# connectors.net
KiCad netlist of a schematic drawn in Altium Designer
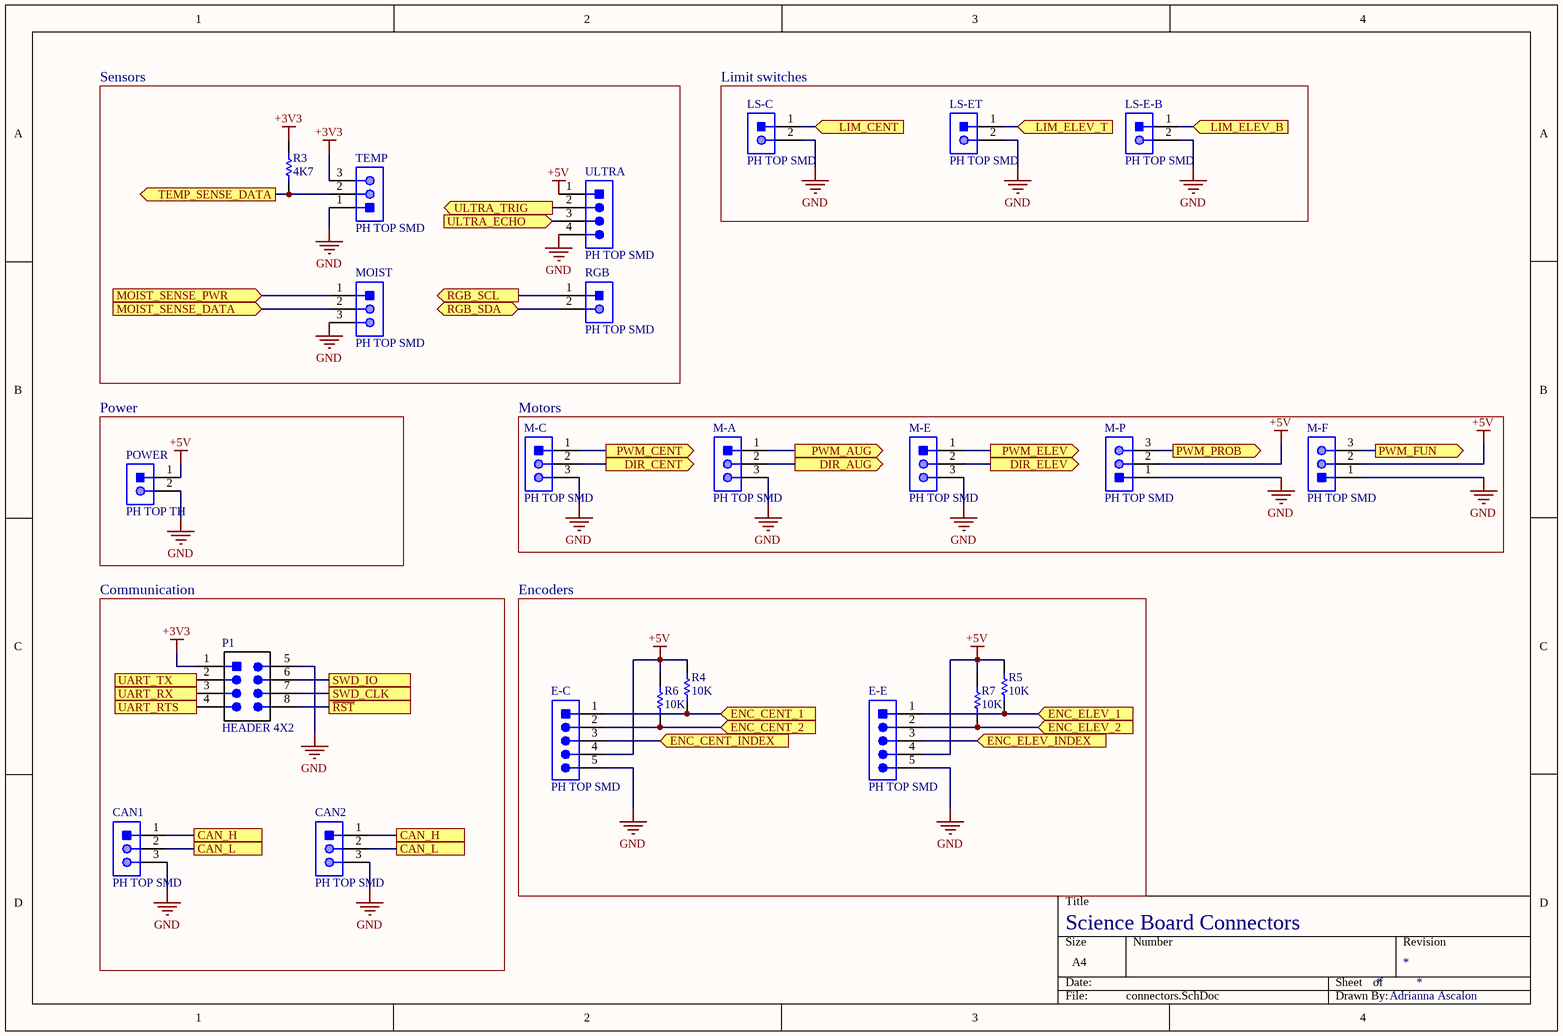
[diagram p0: connectors.SchDoc]

(export (version "E")
  (design (tool "Eeschema 10.0.6"))
  (components
    (comp (ref "CAN1")
      (value "PH TOP SMD")
      (footprint "JST-B3B-SM4-TB")
      (description "CONN HEADER PH TOP 3POS 2MM SMD")
      (fields (field (name "MANUFACTURER") "JST") (field (name "PART NUMBER") "B3B-PH-SM4-TB"))
      (libsource (lib "UWRT_Schematic_Library_2019") (part "CON_3M_PH_TOP_SMT"))
    )
    (comp (ref "CAN2")
      (value "PH TOP SMD")
      (footprint "JST-B3B-SM4-TB")
      (description "CONN HEADER PH TOP 3POS 2MM SMD")
      (fields (field (name "MANUFACTURER") "JST") (field (name "PART NUMBER") "B3B-PH-SM4-TB"))
      (libsource (lib "UWRT_Schematic_Library_2019") (part "CON_3M_PH_TOP_SMT"))
    )
    (comp (ref "E-C")
      (value "PH TOP SMD")
      (footprint "JST-B5B-SM4-TB")
      (description "CONN HEADER PH TOP 5POS 2MM SMD")
      (fields (field (name "MANUFACTURER") "JST") (field (name "PART NUMBER") "B5B-PH-SM4-TB"))
      (libsource (lib "UWRT_Schematic_Library_2019") (part "CON_5M_PH_TOP_SMT"))
    )
    (comp (ref "E-E")
      (value "PH TOP SMD")
      (footprint "JST-B5B-SM4-TB")
      (description "CONN HEADER PH TOP 5POS 2MM SMD")
      (fields (field (name "MANUFACTURER") "JST") (field (name "PART NUMBER") "B5B-PH-SM4-TB"))
      (libsource (lib "UWRT_Schematic_Library_2019") (part "CON_5M_PH_TOP_SMT"))
    )
    (comp (ref "LS-C")
      (value "PH TOP SMD")
      (footprint "JST-B2B-SM4-TB")
      (description "CONN HEADER PH TOP 2POS 2MM SMD")
      (fields (field (name "MANUFACTURER") "JST") (field (name "PART NUMBER") "B2B-PH-SM4-TB"))
      (libsource (lib "UWRT_Schematic_Library_2019") (part "CON_2M_PH_TOP_SMT"))
    )
    (comp (ref "LS-E-B")
      (value "PH TOP SMD")
      (footprint "JST-B2B-SM4-TB")
      (description "CONN HEADER PH TOP 2POS 2MM SMD")
      (fields (field (name "MANUFACTURER") "JST") (field (name "PART NUMBER") "B2B-PH-SM4-TB"))
      (libsource (lib "UWRT_Schematic_Library_2019") (part "CON_2M_PH_TOP_SMT"))
    )
    (comp (ref "LS-ET")
      (value "PH TOP SMD")
      (footprint "JST-B2B-SM4-TB")
      (description "CONN HEADER PH TOP 2POS 2MM SMD")
      (fields (field (name "MANUFACTURER") "JST") (field (name "PART NUMBER") "B2B-PH-SM4-TB"))
      (libsource (lib "UWRT_Schematic_Library_2019") (part "CON_2M_PH_TOP_SMT"))
    )
    (comp (ref "M-A")
      (value "PH TOP SMD")
      (footprint "JST-B3B-SM4-TB")
      (description "CONN HEADER PH TOP 3POS 2MM SMD")
      (fields (field (name "MANUFACTURER") "JST") (field (name "PART NUMBER") "B3B-PH-SM4-TB"))
      (libsource (lib "UWRT_Schematic_Library_2019") (part "CON_3M_PH_TOP_SMT"))
    )
    (comp (ref "M-C")
      (value "PH TOP SMD")
      (footprint "JST-B3B-SM4-TB")
      (description "CONN HEADER PH TOP 3POS 2MM SMD")
      (fields (field (name "MANUFACTURER") "JST") (field (name "PART NUMBER") "B3B-PH-SM4-TB"))
      (libsource (lib "UWRT_Schematic_Library_2019") (part "CON_3M_PH_TOP_SMT"))
    )
    (comp (ref "M-E")
      (value "PH TOP SMD")
      (footprint "JST-B3B-SM4-TB")
      (description "CONN HEADER PH TOP 3POS 2MM SMD")
      (fields (field (name "MANUFACTURER") "JST") (field (name "PART NUMBER") "B3B-PH-SM4-TB"))
      (libsource (lib "UWRT_Schematic_Library_2019") (part "CON_3M_PH_TOP_SMT"))
    )
    (comp (ref "M-F")
      (value "PH TOP SMD")
      (footprint "JST-B3B-SM4-TB")
      (description "CONN HEADER PH TOP 3POS 2MM SMD")
      (fields (field (name "MANUFACTURER") "JST") (field (name "PART NUMBER") "B3B-PH-SM4-TB"))
      (libsource (lib "") (part "CON_3M_PH_TOP_SMT_1"))
    )
    (comp (ref "M-P")
      (value "PH TOP SMD")
      (footprint "JST-B3B-SM4-TB")
      (description "CONN HEADER PH TOP 3POS 2MM SMD")
      (fields (field (name "MANUFACTURER") "JST") (field (name "PART NUMBER") "B3B-PH-SM4-TB"))
      (libsource (lib "") (part "CON_3M_PH_TOP_SMT_1"))
    )
    (comp (ref "MOIST")
      (value "PH TOP SMD")
      (footprint "JST-B3B-SM4-TB")
      (description "CONN HEADER PH TOP 3POS 2MM SMD")
      (fields (field (name "MANUFACTURER") "JST") (field (name "PART NUMBER") "B3B-PH-SM4-TB"))
      (libsource (lib "") (part "CON_3M_PH_TOP_SMT_2"))
    )
    (comp (ref "P1")
      (value "HEADER 4X2")
      (footprint "UWRT_Footprint_Library_2019:HEADER_2X4")
      (description "Header, 4-Pin Dual row")
      (fields (field (name "PUBLISHER") "Altium Limited"))
      (libsource (lib "UWRT_Schematic_Library_2019") (part "HEADER 4X2"))
    )
    (comp (ref "POWER")
      (value "PH TOP TH")
      (footprint "JST-B2B-PHSK")
      (description "CONN HEADER PH TOP 2POS 2MM")
      (fields (field (name "MANUFACTURER") "JST") (field (name "PART NUMBER") "B2B-PH-K-S"))
      (libsource (lib "UWRT_Schematic_Library_2019") (part "CON_2M_PH_TOP_TH"))
    )
    (comp (ref "R3")
      (value "4K7")
      (footprint "RESC0603(1608)_N")
      (description "RES SMD 4.7K OHM 5% 1/10W 0603")
      (fields (field (name "MANUFACTURER") "Yageo") (field (name "TOLERANCE") "5%"))
      (libsource (lib "UWRT_Schematic_Library_2019") (part "RES_4K7_0603"))
    )
    (comp (ref "R4")
      (value "10K")
      (footprint "RESC0603(1608)_N")
      (description "RES SMD 10K OHM 5% 1/10W 0603")
      (fields (field (name "MANUFACTURER") "Yageo") (field (name "TOLERANCE") "5%"))
      (libsource (lib "UWRT_Schematic_Library_2019") (part "RES_10K_0603"))
    )
    (comp (ref "R5")
      (value "10K")
      (footprint "RESC0603(1608)_N")
      (description "RES SMD 10K OHM 5% 1/10W 0603")
      (fields (field (name "MANUFACTURER") "Yageo") (field (name "TOLERANCE") "5%"))
      (libsource (lib "UWRT_Schematic_Library_2019") (part "RES_10K_0603"))
    )
    (comp (ref "R6")
      (value "10K")
      (footprint "RESC0603(1608)_N")
      (description "RES SMD 10K OHM 5% 1/10W 0603")
      (fields (field (name "MANUFACTURER") "Yageo") (field (name "TOLERANCE") "5%"))
      (libsource (lib "UWRT_Schematic_Library_2019") (part "RES_10K_0603"))
    )
    (comp (ref "R7")
      (value "10K")
      (footprint "RESC0603(1608)_N")
      (description "RES SMD 10K OHM 5% 1/10W 0603")
      (fields (field (name "MANUFACTURER") "Yageo") (field (name "TOLERANCE") "5%"))
      (libsource (lib "UWRT_Schematic_Library_2019") (part "RES_10K_0603"))
    )
    (comp (ref "RGB")
      (value "PH TOP SMD")
      (footprint "JST-B2B-SM4-TB")
      (description "CONN HEADER PH TOP 2POS 2MM SMD")
      (fields (field (name "MANUFACTURER") "JST") (field (name "PART NUMBER") "B2B-PH-SM4-TB"))
      (libsource (lib "") (part "CON_2M_PH_TOP_SMT_1"))
    )
    (comp (ref "TEMP")
      (value "PH TOP SMD")
      (footprint "JST-B3B-SM4-TB")
      (description "CONN HEADER PH TOP 3POS 2MM SMD")
      (fields (field (name "MANUFACTURER") "JST") (field (name "PART NUMBER") "B3B-PH-SM4-TB"))
      (libsource (lib "") (part "CON_3M_PH_TOP_SMT_3"))
    )
    (comp (ref "ULTRA")
      (value "PH TOP SMD")
      (footprint "JST-B4B-SM4-TB")
      (description "CONN HEADER PH TOP 4POS 2MM SMD")
      (fields (field (name "MANUFACTURER") "JST") (field (name "PART NUMBER") "B4B-PH-SM4-TB"))
      (libsource (lib "UWRT_Schematic_Library_2019") (part "CON_4M_PH_TOP_SMT"))
    )
  )
  (nets
    (net (code "1") (name "+3V3") (class "Default")
      (node (ref "P1") (pin "1") (pinfunction "VCC_1") (pintype "passive"))
      (node (ref "R3") (pin "2") (pinfunction "2_2") (pintype "passive"))
      (node (ref "TEMP") (pin "3") (pinfunction "3_3") (pintype "passive"))
    )
    (net (code "2") (name "+5V") (class "Default")
      (node (ref "E-C") (pin "4") (pinfunction "4_4") (pintype "passive"))
      (node (ref "E-E") (pin "4") (pinfunction "4_4") (pintype "passive"))
      (node (ref "M-F") (pin "2") (pinfunction "2_2") (pintype "passive"))
      (node (ref "M-P") (pin "2") (pinfunction "2_2") (pintype "passive"))
      (node (ref "POWER") (pin "1") (pinfunction "1_1") (pintype "passive"))
      (node (ref "R4") (pin "2") (pinfunction "2_2") (pintype "passive"))
      (node (ref "R5") (pin "2") (pinfunction "2_2") (pintype "passive"))
      (node (ref "R6") (pin "2") (pinfunction "2_2") (pintype "passive"))
      (node (ref "R7") (pin "2") (pinfunction "2_2") (pintype "passive"))
      (node (ref "ULTRA") (pin "1") (pinfunction "1_1") (pintype "passive"))
    )
    (net (code "3") (name "/CAN_H") (class "Default")
      (node (ref "CAN1") (pin "1") (pinfunction "1_1") (pintype "passive"))
      (node (ref "CAN2") (pin "1") (pinfunction "1_1") (pintype "passive"))
    )
    (net (code "4") (name "/CAN_L") (class "Default")
      (node (ref "CAN1") (pin "2") (pinfunction "2_2") (pintype "passive"))
      (node (ref "CAN2") (pin "2") (pinfunction "2_2") (pintype "passive"))
    )
    (net (code "5") (name "/DIR_AUG") (class "Default")
      (node (ref "M-A") (pin "2") (pinfunction "2_2") (pintype "passive"))
    )
    (net (code "6") (name "/DIR_CENT") (class "Default")
      (node (ref "M-C") (pin "2") (pinfunction "2_2") (pintype "passive"))
    )
    (net (code "7") (name "/DIR_ELEV") (class "Default")
      (node (ref "M-E") (pin "2") (pinfunction "2_2") (pintype "passive"))
    )
    (net (code "8") (name "/ENC_CENT_1") (class "Default")
      (node (ref "E-C") (pin "1") (pinfunction "1_1") (pintype "passive"))
      (node (ref "R4") (pin "1") (pinfunction "1_1") (pintype "passive"))
    )
    (net (code "9") (name "/ENC_CENT_2") (class "Default")
      (node (ref "E-C") (pin "2") (pinfunction "2_2") (pintype "passive"))
      (node (ref "R6") (pin "1") (pinfunction "1_1") (pintype "passive"))
    )
    (net (code "10") (name "/ENC_CENT_INDEX") (class "Default")
      (node (ref "E-C") (pin "3") (pinfunction "3_3") (pintype "passive"))
    )
    (net (code "11") (name "/ENC_ELEV_1") (class "Default")
      (node (ref "E-E") (pin "1") (pinfunction "1_1") (pintype "passive"))
      (node (ref "R5") (pin "1") (pinfunction "1_1") (pintype "passive"))
    )
    (net (code "12") (name "/ENC_ELEV_2") (class "Default")
      (node (ref "E-E") (pin "2") (pinfunction "2_2") (pintype "passive"))
      (node (ref "R7") (pin "1") (pinfunction "1_1") (pintype "passive"))
    )
    (net (code "13") (name "/ENC_ELEV_INDEX") (class "Default")
      (node (ref "E-E") (pin "3") (pinfunction "3_3") (pintype "passive"))
    )
    (net (code "14") (name "/LIM_CENT") (class "Default")
      (node (ref "LS-C") (pin "1") (pinfunction "1_1") (pintype "passive"))
    )
    (net (code "15") (name "/LIM_ELEV_B") (class "Default")
      (node (ref "LS-E-B") (pin "1") (pinfunction "1_1") (pintype "passive"))
    )
    (net (code "16") (name "/LIM_ELEV_T") (class "Default")
      (node (ref "LS-ET") (pin "1") (pinfunction "1_1") (pintype "passive"))
    )
    (net (code "17") (name "/MOIST_SENSE_DATA") (class "Default")
      (node (ref "MOIST") (pin "2") (pinfunction "2_2") (pintype "passive"))
    )
    (net (code "18") (name "/MOIST_SENSE_PWR") (class "Default")
      (node (ref "MOIST") (pin "1") (pinfunction "1_1") (pintype "passive"))
    )
    (net (code "19") (name "/PWM_AUG") (class "Default")
      (node (ref "M-A") (pin "1") (pinfunction "1_1") (pintype "passive"))
    )
    (net (code "20") (name "/PWM_CENT") (class "Default")
      (node (ref "M-C") (pin "1") (pinfunction "1_1") (pintype "passive"))
    )
    (net (code "21") (name "/PWM_ELEV") (class "Default")
      (node (ref "M-E") (pin "1") (pinfunction "1_1") (pintype "passive"))
    )
    (net (code "22") (name "/PWM_FUN") (class "Default")
      (node (ref "M-F") (pin "3") (pinfunction "3_3") (pintype "passive"))
    )
    (net (code "23") (name "/PWM_PROB") (class "Default")
      (node (ref "M-P") (pin "3") (pinfunction "3_3") (pintype "passive"))
    )
    (net (code "24") (name "/RGB_SCL") (class "Default")
      (node (ref "RGB") (pin "1") (pinfunction "1_1") (pintype "passive"))
    )
    (net (code "25") (name "/RGB_SDA") (class "Default")
      (node (ref "RGB") (pin "2") (pinfunction "2_2") (pintype "passive"))
    )
    (net (code "26") (name "/SWD_CLK") (class "Default")
      (node (ref "P1") (pin "7") (pinfunction "3_7") (pintype "passive"))
    )
    (net (code "27") (name "/SWD_IO") (class "Default")
      (node (ref "P1") (pin "6") (pinfunction "2_6") (pintype "passive"))
    )
    (net (code "28") (name "/TEMP_SENSE_DATA") (class "Default")
      (node (ref "R3") (pin "1") (pinfunction "1_1") (pintype "passive"))
      (node (ref "TEMP") (pin "2") (pinfunction "2_2") (pintype "passive"))
    )
    (net (code "29") (name "/UART_RTS") (class "Default")
      (node (ref "P1") (pin "4") (pinfunction "4_4") (pintype "passive"))
    )
    (net (code "30") (name "/UART_RX") (class "Default")
      (node (ref "P1") (pin "3") (pinfunction "3_3") (pintype "passive"))
    )
    (net (code "31") (name "/UART_TX") (class "Default")
      (node (ref "P1") (pin "2") (pinfunction "2_2") (pintype "passive"))
    )
    (net (code "32") (name "/ULTRA_ECHO") (class "Default")
      (node (ref "ULTRA") (pin "3") (pinfunction "3_3") (pintype "passive"))
    )
    (net (code "33") (name "/ULTRA_TRIG") (class "Default")
      (node (ref "ULTRA") (pin "2") (pinfunction "2_2") (pintype "passive"))
    )
    (net (code "34") (name "/~{RST}") (class "Default")
      (node (ref "P1") (pin "8") (pinfunction "4_8") (pintype "passive"))
    )
    (net (code "35") (name "GND") (class "Default")
      (node (ref "CAN1") (pin "3") (pinfunction "3_3") (pintype "passive"))
      (node (ref "CAN2") (pin "3") (pinfunction "3_3") (pintype "passive"))
      (node (ref "E-C") (pin "5") (pinfunction "5_5") (pintype "passive"))
      (node (ref "E-E") (pin "5") (pinfunction "5_5") (pintype "passive"))
      (node (ref "LS-C") (pin "2") (pinfunction "2_2") (pintype "passive"))
      (node (ref "LS-E-B") (pin "2") (pinfunction "2_2") (pintype "passive"))
      (node (ref "LS-ET") (pin "2") (pinfunction "2_2") (pintype "passive"))
      (node (ref "M-A") (pin "3") (pinfunction "3_3") (pintype "passive"))
      (node (ref "M-C") (pin "3") (pinfunction "3_3") (pintype "passive"))
      (node (ref "M-E") (pin "3") (pinfunction "3_3") (pintype "passive"))
      (node (ref "M-F") (pin "1") (pinfunction "1_1") (pintype "passive"))
      (node (ref "M-P") (pin "1") (pinfunction "1_1") (pintype "passive"))
      (node (ref "MOIST") (pin "3") (pinfunction "3_3") (pintype "passive"))
      (node (ref "P1") (pin "5") (pinfunction "GND_5") (pintype "passive"))
      (node (ref "POWER") (pin "2") (pinfunction "2_2") (pintype "passive"))
      (node (ref "TEMP") (pin "1") (pinfunction "1_1") (pintype "passive"))
      (node (ref "ULTRA") (pin "4") (pinfunction "4_4") (pintype "passive"))
    )
  )
)
